# Power_Distribution_-_Roof_Enclosure.net
KiCad netlist of a schematic drawn in Altium Designer
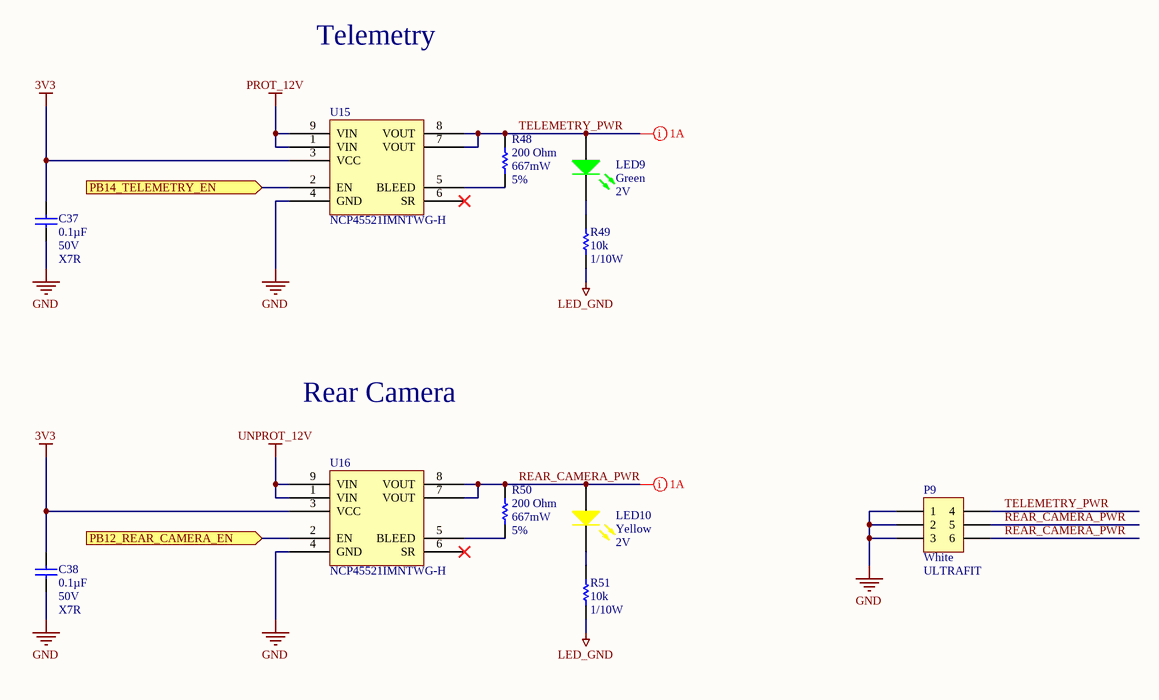
[diagram p0: Power Distribution - Roof Enclosure.SchDoc]

(export (version "E")
  (design (tool "Eeschema 10.0.6"))
  (components
    (comp (ref "C37")
      (value "CAP CER 0.1UF 50V 10% X7R 0603")
      (footprint "CAP, 0603")
      (description "0.10µF ±10% 50V Ceramic Capacitor X7R 0603 (1608 Metric)")
      (fields
        (field (name "TOLERANCE") "±10%")
        (field (name "CAPACITANCE") "0.1µF")
        (field (name "VOLTAGE") "50V")
        (field (name "TEMPERATURE COEFFICIENT") "X7R")
      )
      (libsource (lib "Schematic Diagrams") (part "CAP CER 0.1UF 50V 10% X7R 0603"))
    )
    (comp (ref "C38")
      (value "CAP CER 0.1UF 50V 10% X7R 0603")
      (footprint "CAP, 0603")
      (description "0.10µF ±10% 50V Ceramic Capacitor X7R 0603 (1608 Metric)")
      (fields
        (field (name "TOLERANCE") "±10%")
        (field (name "CAPACITANCE") "0.1µF")
        (field (name "VOLTAGE") "50V")
        (field (name "TEMPERATURE COEFFICIENT") "X7R")
      )
      (libsource (lib "Schematic Diagrams") (part "CAP CER 0.1UF 50V 10% X7R 0603"))
    )
    (comp (ref "LED9")
      (value "LED GREEN CLEAR 2V 0603")
      (footprint "LED_0603")
      (description "Green 572nm LED Indication - Discrete 2V 0603 (1608 Metric)")
      (fields
        (field (name "MANUFACTURER") "Wurth Electronics Inc.")
        (field (name "MANUFACTURER PART NUMBER") "150060VS75000")
        (field (name "COLOR") "Green")
        (field (name "VOLTAGE - FORWARD (VF) (TYP)") "2V")
      )
      (libsource (lib "Schematic Diagrams") (part "LED GREEN CLEAR 2V 0603"))
    )
    (comp (ref "LED10")
      (value "LED YELLOW CLEAR 2.1V 0603")
      (footprint "LED_0603")
      (description "Yellow 590nm LED Indication - Discrete 2V 0603 (1608 Metric)")
      (fields
        (field (name "MANUFACTURER") "Wurth Electronics Inc.")
        (field (name "MANUFACTURER PART NUMBER") "150060YS75000")
        (field (name "COLOR") "Yellow")
        (field (name "VOLTAGE - FORWARD (VF) (TYP)") "2V")
      )
      (libsource (lib "Schematic Diagrams") (part "LED YELLOW CLEAR 2.1V 0603"))
    )
    (comp (ref "P9")
      (value "CONN 6POS ULTRA-FIT NATURAL COLOR 0.138\"")
      (footprint "CONN, 6POS ULTRA-FIT - NATURAL COLOR")
      (description "6 Positions Header Connector 0.138\" (3.50mm) Through Hole Tin")
      (fields (field (name "INSULATION COLOR") "White") (field (name "SERIES") "ULTRAFIT"))
      (libsource (lib "Schematic Diagrams") (part "CONN 6POS ULTRA-FIT NATURAL COLOR 0.138{dblquote}"))
    )
    (comp (ref "R48")
      (value "200 Ohm")
      (footprint "RES 1206")
      (fields
        (field (name "MANUFACTURER") "Panasonic")
        (field (name "MANUFACTURER PART NUMBER") "ERJ-P08J201V")
        (field (name "TOLERANCE") "5%")
        (field (name "MAX POWER DISSIPATION") "667mW")
      )
      (libsource (lib "Schematic Diagrams") (part "RES 200 OHM 5% 2/3W 1206"))
    )
    (comp (ref "R49")
      (value "RES 10K OHM 1% 1/10W 0603")
      (footprint "RES, 0603")
      (description "RES SMD 10K OHM 1% 1/10W 0603")
      (fields
        (field (name "TOLERANCE") "±1%")
        (field (name "RESISTANCE") "10k")
        (field (name "POWER") "1/10W")
      )
      (libsource (lib "Schematic Diagrams") (part "RES 10K OHM 1% 1/10W 0603"))
    )
    (comp (ref "R50")
      (value "200 Ohm")
      (footprint "RES 1206")
      (fields
        (field (name "MANUFACTURER") "Panasonic")
        (field (name "MANUFACTURER PART NUMBER") "ERJ-P08J201V")
        (field (name "TOLERANCE") "5%")
        (field (name "MAX POWER DISSIPATION") "667mW")
      )
      (libsource (lib "Schematic Diagrams") (part "RES 200 OHM 5% 2/3W 1206"))
    )
    (comp (ref "R51")
      (value "RES 10K OHM 1% 1/10W 0603")
      (footprint "RES, 0603")
      (description "RES SMD 10K OHM 1% 1/10W 0603")
      (fields
        (field (name "TOLERANCE") "±1%")
        (field (name "RESISTANCE") "10k")
        (field (name "POWER") "1/10W")
      )
      (libsource (lib "Schematic Diagrams") (part "RES 10K OHM 1% 1/10W 0603"))
    )
    (comp (ref "U15")
      (value "IC LOAD SWITCH ACT-HI 10.5A 8DFN")
      (footprint "IC LOAD SWITCH ACT-HI 10.5A 8DFN")
      (description "NCP45521IMNTWG-H")
      (fields
        (field (name "MANUFACTURER") "ON Semiconductor")
        (field (name "MANUFACTURER PART NUMBER") "NCP45521IMNTWG-H")
      )
      (libsource (lib "Schematic Diagrams") (part "IC LOAD SWITCH ACT-HI 10.5A 8DFN"))
    )
    (comp (ref "U16")
      (value "IC LOAD SWITCH ACT-HI 10.5A 8DFN")
      (footprint "IC LOAD SWITCH ACT-HI 10.5A 8DFN")
      (description "NCP45521IMNTWG-H")
      (fields
        (field (name "MANUFACTURER") "ON Semiconductor")
        (field (name "MANUFACTURER PART NUMBER") "NCP45521IMNTWG-H")
      )
      (libsource (lib "Schematic Diagrams") (part "IC LOAD SWITCH ACT-HI 10.5A 8DFN"))
    )
  )
  (nets
    (net (code "1") (name "/PB12_REAR_CAMERA_EN") (class "Default")
      (node (ref "U16") (pin "2") (pinfunction "EN_2") (pintype "passive"))
    )
    (net (code "2") (name "/PB14_TELEMETRY_EN") (class "Default")
      (node (ref "U15") (pin "2") (pinfunction "EN_2") (pintype "passive"))
    )
    (net (code "3") (name "/REAR_CAMERA_PWR") (class "Default")
      (node (ref "LED10") (pin "1") (pinfunction "A_1") (pintype "passive"))
      (node (ref "P9") (pin "5") (pinfunction "5_5") (pintype "passive"))
      (node (ref "P9") (pin "6") (pinfunction "6_6") (pintype "passive"))
      (node (ref "R50") (pin "1") (pinfunction "1_1") (pintype "passive"))
      (node (ref "U16") (pin "7") (pinfunction "VOUT_7") (pintype "passive"))
      (node (ref "U16") (pin "8") (pinfunction "VOUT_8") (pintype "passive"))
    )
    (net (code "4") (name "/TELEMETRY_PWR") (class "Default")
      (node (ref "LED9") (pin "1") (pinfunction "A_1") (pintype "passive"))
      (node (ref "P9") (pin "4") (pinfunction "4_4") (pintype "passive"))
      (node (ref "R48") (pin "1") (pinfunction "1_1") (pintype "passive"))
      (node (ref "U15") (pin "7") (pinfunction "VOUT_7") (pintype "passive"))
      (node (ref "U15") (pin "8") (pinfunction "VOUT_8") (pintype "passive"))
    )
    (net (code "5") (name "3V3") (class "Default")
      (node (ref "C37") (pin "1") (pinfunction "1_1") (pintype "passive"))
      (node (ref "C38") (pin "1") (pinfunction "1_1") (pintype "passive"))
      (node (ref "U15") (pin "3") (pinfunction "VCC_3") (pintype "passive"))
      (node (ref "U16") (pin "3") (pinfunction "VCC_3") (pintype "passive"))
    )
    (net (code "6") (name "GND") (class "Default")
      (node (ref "C37") (pin "2") (pinfunction "2_2") (pintype "passive"))
      (node (ref "C38") (pin "2") (pinfunction "2_2") (pintype "passive"))
      (node (ref "P9") (pin "1") (pinfunction "1_1") (pintype "passive"))
      (node (ref "P9") (pin "2") (pinfunction "2_2") (pintype "passive"))
      (node (ref "P9") (pin "3") (pinfunction "3_3") (pintype "passive"))
      (node (ref "U15") (pin "4") (pinfunction "GND_4") (pintype "passive"))
      (node (ref "U16") (pin "4") (pinfunction "GND_4") (pintype "passive"))
    )
    (net (code "7") (name "LED_GND") (class "Default")
      (node (ref "R49") (pin "2") (pinfunction "2_2") (pintype "passive"))
      (node (ref "R51") (pin "2") (pinfunction "2_2") (pintype "passive"))
    )
    (net (code "8") (name "Net-(LED9-K)") (class "Default")
      (node (ref "LED9") (pin "2") (pinfunction "K_2") (pintype "passive"))
      (node (ref "R49") (pin "1") (pinfunction "1_1") (pintype "passive"))
    )
    (net (code "9") (name "Net-(LED10-K)") (class "Default")
      (node (ref "LED10") (pin "2") (pinfunction "K_2") (pintype "passive"))
      (node (ref "R51") (pin "1") (pinfunction "1_1") (pintype "passive"))
    )
    (net (code "10") (name "Net-(U15-BLEED)") (class "Default")
      (node (ref "R48") (pin "2") (pinfunction "2_2") (pintype "passive"))
      (node (ref "U15") (pin "5") (pinfunction "BLEED_5") (pintype "passive"))
    )
    (net (code "11") (name "Net-(U16-BLEED)") (class "Default")
      (node (ref "R50") (pin "2") (pinfunction "2_2") (pintype "passive"))
      (node (ref "U16") (pin "5") (pinfunction "BLEED_5") (pintype "passive"))
    )
    (net (code "12") (name "PROT_12V") (class "Default")
      (node (ref "U15") (pin "1") (pinfunction "VIN_1") (pintype "passive"))
      (node (ref "U15") (pin "9") (pinfunction "VIN_9") (pintype "passive"))
    )
    (net (code "13") (name "UNPROT_12V") (class "Default")
      (node (ref "U16") (pin "1") (pinfunction "VIN_1") (pintype "passive"))
      (node (ref "U16") (pin "9") (pinfunction "VIN_9") (pintype "passive"))
    )
    (net (code "14") (name "unconnected-(U15-SR-Pad6)") (class "Default")
      (node (ref "U15") (pin "6") (pinfunction "SR_6") (pintype "passive+no_connect"))
    )
    (net (code "15") (name "unconnected-(U16-SR-Pad6)") (class "Default")
      (node (ref "U16") (pin "6") (pinfunction "SR_6") (pintype "passive+no_connect"))
    )
  )
)
